# EIS_Main_Radio.net
KiCad netlist of a schematic drawn in Altium Designer
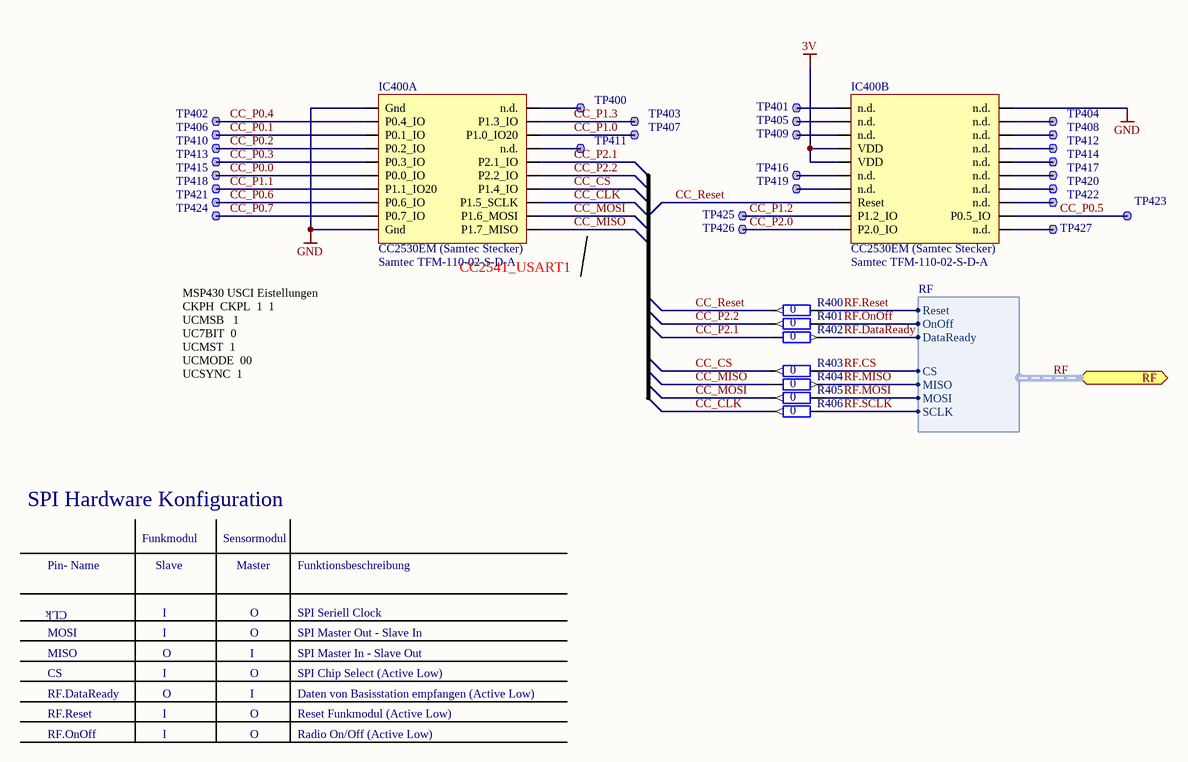
[diagram p0: EIS_Main_Radio.SchDoc]

(export (version "E")
  (design (tool "Eeschema 10.0.6"))
  (components
    (comp (ref "IC400")
      (value "CC2530EM (Samtec Stecker)")
      (footprint "CC2400EM_Board")
      (description "CC2530EM Referenzdesign, Samtec TFM-110-02-S-D-A")
      (fields
        (field (name "01_HERSTELLER") "Samtec TFM-110-02-S-D-A")
        (field (name "09_ERSTELLER") "HSG Rachid Nouna")
      )
      (libsource (lib "RudiSchlibAllg") (part "CC2530EM"))
    )
    (comp (ref "R400")
      (value "0")
      (footprint "RESC1608N")
      (description "RESC1608 (R0603)")
      (libsource (lib "JM_Widerstaende") (part "RESC1608 (R0603)"))
    )
    (comp (ref "R401")
      (value "0")
      (footprint "RESC1608N")
      (description "RESC1608 (R0603)")
      (libsource (lib "JM_Widerstaende") (part "RESC1608 (R0603)"))
    )
    (comp (ref "R402")
      (value "0")
      (footprint "RESC1608N")
      (description "RESC1608 (R0603)")
      (libsource (lib "JM_Widerstaende") (part "RESC1608 (R0603)"))
    )
    (comp (ref "R403")
      (value "0")
      (footprint "RESC1608N")
      (description "RESC1608 (R0603)")
      (libsource (lib "JM_Widerstaende") (part "RESC1608 (R0603)"))
    )
    (comp (ref "R404")
      (value "0")
      (footprint "RESC1608N")
      (description "RESC1608 (R0603)")
      (libsource (lib "JM_Widerstaende") (part "RESC1608 (R0603)"))
    )
    (comp (ref "R405")
      (value "0")
      (footprint "RESC1608N")
      (description "RESC1608 (R0603)")
      (libsource (lib "JM_Widerstaende") (part "RESC1608 (R0603)"))
    )
    (comp (ref "R406")
      (value "0")
      (footprint "RESC1608N")
      (description "RESC1608 (R0603)")
      (libsource (lib "JM_Widerstaende") (part "RESC1608 (R0603)"))
    )
    (comp (ref "TP400")
      (value "Testpoint 1mm")
      (footprint "Testpoint 1mm")
      (libsource (lib "HSG-IMIT_JuergenMerz") (part "Tespoint 1mm"))
    )
    (comp (ref "TP401")
      (value "Testpoint 1mm")
      (footprint "Testpoint 1mm")
      (libsource (lib "HSG-IMIT_JuergenMerz") (part "Tespoint 1mm"))
    )
    (comp (ref "TP402")
      (value "Testpoint 1mm")
      (footprint "Testpoint 1mm")
      (libsource (lib "HSG-IMIT_JuergenMerz") (part "Tespoint 1mm"))
    )
    (comp (ref "TP403")
      (value "Testpoint 1mm")
      (footprint "Testpoint 1mm")
      (libsource (lib "HSG-IMIT_JuergenMerz") (part "Tespoint 1mm"))
    )
    (comp (ref "TP404")
      (value "Testpoint 1mm")
      (footprint "Testpoint 1mm")
      (libsource (lib "HSG-IMIT_JuergenMerz") (part "Tespoint 1mm"))
    )
    (comp (ref "TP405")
      (value "Testpoint 1mm")
      (footprint "Testpoint 1mm")
      (libsource (lib "HSG-IMIT_JuergenMerz") (part "Tespoint 1mm"))
    )
    (comp (ref "TP406")
      (value "Testpoint 1mm")
      (footprint "Testpoint 1mm")
      (libsource (lib "HSG-IMIT_JuergenMerz") (part "Tespoint 1mm"))
    )
    (comp (ref "TP407")
      (value "Testpoint 1mm")
      (footprint "Testpoint 1mm")
      (libsource (lib "HSG-IMIT_JuergenMerz") (part "Tespoint 1mm"))
    )
    (comp (ref "TP408")
      (value "Testpoint 1mm")
      (footprint "Testpoint 1mm")
      (libsource (lib "HSG-IMIT_JuergenMerz") (part "Tespoint 1mm"))
    )
    (comp (ref "TP409")
      (value "Testpoint 1mm")
      (footprint "Testpoint 1mm")
      (libsource (lib "HSG-IMIT_JuergenMerz") (part "Tespoint 1mm"))
    )
    (comp (ref "TP410")
      (value "Testpoint 1mm")
      (footprint "Testpoint 1mm")
      (libsource (lib "HSG-IMIT_JuergenMerz") (part "Tespoint 1mm"))
    )
    (comp (ref "TP411")
      (value "Testpoint 1mm")
      (footprint "Testpoint 1mm")
      (libsource (lib "HSG-IMIT_JuergenMerz") (part "Tespoint 1mm"))
    )
    (comp (ref "TP412")
      (value "Testpoint 1mm")
      (footprint "Testpoint 1mm")
      (libsource (lib "HSG-IMIT_JuergenMerz") (part "Tespoint 1mm"))
    )
    (comp (ref "TP413")
      (value "Testpoint 1mm")
      (footprint "Testpoint 1mm")
      (libsource (lib "HSG-IMIT_JuergenMerz") (part "Tespoint 1mm"))
    )
    (comp (ref "TP414")
      (value "Testpoint 1mm")
      (footprint "Testpoint 1mm")
      (libsource (lib "HSG-IMIT_JuergenMerz") (part "Tespoint 1mm"))
    )
    (comp (ref "TP415")
      (value "Testpoint 1mm")
      (footprint "Testpoint 1mm")
      (libsource (lib "HSG-IMIT_JuergenMerz") (part "Tespoint 1mm"))
    )
    (comp (ref "TP416")
      (value "Testpoint 1mm")
      (footprint "Testpoint 1mm")
      (libsource (lib "HSG-IMIT_JuergenMerz") (part "Tespoint 1mm"))
    )
    (comp (ref "TP417")
      (value "Testpoint 1mm")
      (footprint "Testpoint 1mm")
      (libsource (lib "HSG-IMIT_JuergenMerz") (part "Tespoint 1mm"))
    )
    (comp (ref "TP418")
      (value "Testpoint 1mm")
      (footprint "Testpoint 1mm")
      (libsource (lib "HSG-IMIT_JuergenMerz") (part "Tespoint 1mm"))
    )
    (comp (ref "TP419")
      (value "Testpoint 1mm")
      (footprint "Testpoint 1mm")
      (libsource (lib "HSG-IMIT_JuergenMerz") (part "Tespoint 1mm"))
    )
    (comp (ref "TP420")
      (value "Testpoint 1mm")
      (footprint "Testpoint 1mm")
      (libsource (lib "HSG-IMIT_JuergenMerz") (part "Tespoint 1mm"))
    )
    (comp (ref "TP421")
      (value "Testpoint 1mm")
      (footprint "Testpoint 1mm")
      (libsource (lib "HSG-IMIT_JuergenMerz") (part "Tespoint 1mm"))
    )
    (comp (ref "TP422")
      (value "Testpoint 1mm")
      (footprint "Testpoint 1mm")
      (libsource (lib "HSG-IMIT_JuergenMerz") (part "Tespoint 1mm"))
    )
    (comp (ref "TP423")
      (value "Testpoint 1mm")
      (footprint "Testpoint 1mm")
      (libsource (lib "HSG-IMIT_JuergenMerz") (part "Tespoint 1mm"))
    )
    (comp (ref "TP424")
      (value "Testpoint 1mm")
      (footprint "Testpoint 1mm")
      (libsource (lib "HSG-IMIT_JuergenMerz") (part "Tespoint 1mm"))
    )
    (comp (ref "TP425")
      (value "Testpoint 1mm")
      (footprint "Testpoint 1mm")
      (libsource (lib "HSG-IMIT_JuergenMerz") (part "Tespoint 1mm"))
    )
    (comp (ref "TP426")
      (value "Testpoint 1mm")
      (footprint "Testpoint 1mm")
      (libsource (lib "HSG-IMIT_JuergenMerz") (part "Tespoint 1mm"))
    )
    (comp (ref "TP427")
      (value "Testpoint 1mm")
      (footprint "Testpoint 1mm")
      (libsource (lib "HSG-IMIT_JuergenMerz") (part "Tespoint 1mm"))
    )
  )
  (nets
    (net (code "2") (name "/CC_CLK") (class "Default")
      (node (ref "IC400") (pin "P1_16") (pinfunction "P1.5_SCLK_P1_16") (pintype "passive"))
      (node (ref "R406") (pin "1") (pinfunction "1_1") (pintype "output"))
    )
    (net (code "3") (name "/CC_CS") (class "Default")
      (node (ref "IC400") (pin "P1_14") (pinfunction "P1.4_IO_P1_14") (pintype "passive"))
      (node (ref "R403") (pin "1") (pinfunction "1_1") (pintype "output"))
    )
    (net (code "4") (name "/CC_MISO") (class "Default")
      (node (ref "IC400") (pin "P1_20") (pinfunction "P1.7_MISO_P1_20") (pintype "passive"))
      (node (ref "R404") (pin "1") (pinfunction "1_1") (pintype "output"))
    )
    (net (code "5") (name "/CC_MOSI") (class "Default")
      (node (ref "IC400") (pin "P1_18") (pinfunction "P1.6_MOSI_P1_18") (pintype "passive"))
      (node (ref "R405") (pin "1") (pinfunction "1_1") (pintype "output"))
    )
    (net (code "6") (name "/CC_P0.0") (class "Default")
      (node (ref "IC400") (pin "P1_11") (pinfunction "P0.0_IO_P1_11") (pintype "passive"))
      (node (ref "TP415") (pin "1") (pintype "passive"))
    )
    (net (code "7") (name "/CC_P0.1") (class "Default")
      (node (ref "IC400") (pin "P1_5") (pinfunction "P0.1_IO_P1_5") (pintype "passive"))
      (node (ref "TP406") (pin "1") (pintype "passive"))
    )
    (net (code "8") (name "/CC_P0.2") (class "Default")
      (node (ref "IC400") (pin "P1_7") (pinfunction "P0.2_IO_P1_7") (pintype "passive"))
      (node (ref "TP410") (pin "1") (pintype "passive"))
    )
    (net (code "9") (name "/CC_P0.3") (class "Default")
      (node (ref "IC400") (pin "P1_9") (pinfunction "P0.3_IO_P1_9") (pintype "passive"))
      (node (ref "TP413") (pin "1") (pintype "passive"))
    )
    (net (code "10") (name "/CC_P0.4") (class "Default")
      (node (ref "IC400") (pin "P1_3") (pinfunction "P0.4_IO_P1_3") (pintype "passive"))
      (node (ref "TP402") (pin "1") (pintype "passive"))
    )
    (net (code "11") (name "/CC_P0.5") (class "Default")
      (node (ref "IC400") (pin "P2_18") (pinfunction "P0.5_IO_P2_18") (pintype "passive"))
      (node (ref "TP423") (pin "1") (pintype "passive"))
    )
    (net (code "12") (name "/CC_P0.6") (class "Default")
      (node (ref "IC400") (pin "P1_15") (pinfunction "P0.6_IO_P1_15") (pintype "passive"))
      (node (ref "TP421") (pin "1") (pintype "passive"))
    )
    (net (code "13") (name "/CC_P0.7") (class "Default")
      (node (ref "IC400") (pin "P1_17") (pinfunction "P0.7_IO_P1_17") (pintype "passive"))
      (node (ref "TP424") (pin "1") (pintype "passive"))
    )
    (net (code "14") (name "/CC_P1.0") (class "Default")
      (node (ref "IC400") (pin "P1_6") (pinfunction "P1.0_IO20_P1_6") (pintype "passive"))
      (node (ref "TP407") (pin "1") (pintype "passive"))
    )
    (net (code "15") (name "/CC_P1.1") (class "Default")
      (node (ref "IC400") (pin "P1_13") (pinfunction "P1.1_IO20_P1_13") (pintype "passive"))
      (node (ref "TP418") (pin "1") (pintype "passive"))
    )
    (net (code "16") (name "/CC_P1.2") (class "Default")
      (node (ref "IC400") (pin "P2_17") (pinfunction "P1.2_IO_P2_17") (pintype "passive"))
      (node (ref "TP425") (pin "1") (pintype "passive"))
    )
    (net (code "17") (name "/CC_P1.3") (class "Default")
      (node (ref "IC400") (pin "P1_4") (pinfunction "P1.3_IO_P1_4") (pintype "passive"))
      (node (ref "TP403") (pin "1") (pintype "passive"))
    )
    (net (code "18") (name "/CC_P2.0") (class "Default")
      (node (ref "IC400") (pin "P2_19") (pinfunction "P2.0_IO_P2_19") (pintype "passive"))
      (node (ref "TP426") (pin "1") (pintype "passive"))
    )
    (net (code "19") (name "/CC_P2.1") (class "Default")
      (node (ref "IC400") (pin "P1_10") (pinfunction "P2.1_IO_P1_10") (pintype "passive"))
      (node (ref "R402") (pin "1") (pinfunction "1_1") (pintype "output"))
    )
    (net (code "20") (name "/CC_P2.2") (class "Default")
      (node (ref "IC400") (pin "P1_12") (pinfunction "P2.2_IO_P1_12") (pintype "passive"))
      (node (ref "R401") (pin "1") (pinfunction "1_1") (pintype "output"))
    )
    (net (code "21") (name "/CC_Reset") (class "Default")
      (node (ref "IC400") (pin "P2_15") (pinfunction "Reset_P2_15") (pintype "passive"))
      (node (ref "R400") (pin "1") (pinfunction "1_1") (pintype "output"))
    )
    (net (code "22") (name "/RF.CS") (class "Default")
      (node (ref "R403") (pin "2") (pinfunction "2_2") (pintype "passive"))
    )
    (net (code "23") (name "/RF.DataReady") (class "Default")
      (node (ref "R402") (pin "2") (pinfunction "2_2") (pintype "passive"))
    )
    (net (code "24") (name "/RF.MISO") (class "Default")
      (node (ref "R404") (pin "2") (pinfunction "2_2") (pintype "passive"))
    )
    (net (code "25") (name "/RF.MOSI") (class "Default")
      (node (ref "R405") (pin "2") (pinfunction "2_2") (pintype "passive"))
    )
    (net (code "26") (name "/RF.OnOff") (class "Default")
      (node (ref "R401") (pin "2") (pinfunction "2_2") (pintype "passive"))
    )
    (net (code "27") (name "/RF.Reset") (class "Default")
      (node (ref "R400") (pin "2") (pinfunction "2_2") (pintype "passive"))
    )
    (net (code "28") (name "/RF.SCLK") (class "Default")
      (node (ref "R406") (pin "2") (pinfunction "2_2") (pintype "passive"))
    )
    (net (code "30") (name "3V") (class "Default")
      (node (ref "IC400") (pin "P2_7") (pinfunction "VDD_P2_7") (pintype "power_in"))
      (node (ref "IC400") (pin "P2_9") (pinfunction "VDD_P2_9") (pintype "power_in"))
    )
    (net (code "31") (name "GND") (class "Default")
      (node (ref "IC400") (pin "P1_1") (pinfunction "Gnd_P1_1") (pintype "power_in"))
      (node (ref "IC400") (pin "P1_19") (pinfunction "Gnd_P1_19") (pintype "power_in"))
      (node (ref "IC400") (pin "P2_2") (pinfunction "n.d._P2_2") (pintype "passive"))
    )
    (net (code "32") (name "Net-(IC400A-n.d.-PadP1_2)") (class "Default")
      (node (ref "IC400") (pin "P1_2") (pinfunction "n.d._P1_2") (pintype "passive"))
      (node (ref "TP400") (pin "1") (pintype "passive"))
    )
    (net (code "33") (name "Net-(IC400A-n.d.-PadP1_8)") (class "Default")
      (node (ref "IC400") (pin "P1_8") (pinfunction "n.d._P1_8") (pintype "passive"))
      (node (ref "TP411") (pin "1") (pintype "passive"))
    )
    (net (code "34") (name "Net-(IC400B-n.d.-PadP2_1)") (class "Default")
      (node (ref "IC400") (pin "P2_1") (pinfunction "n.d._P2_1") (pintype "passive"))
      (node (ref "TP401") (pin "1") (pintype "passive"))
    )
    (net (code "35") (name "Net-(IC400B-n.d.-PadP2_3)") (class "Default")
      (node (ref "IC400") (pin "P2_3") (pinfunction "n.d._P2_3") (pintype "passive"))
      (node (ref "TP405") (pin "1") (pintype "passive"))
    )
    (net (code "36") (name "Net-(IC400B-n.d.-PadP2_4)") (class "Default")
      (node (ref "IC400") (pin "P2_4") (pinfunction "n.d._P2_4") (pintype "passive"))
      (node (ref "TP404") (pin "1") (pintype "passive"))
    )
    (net (code "37") (name "Net-(IC400B-n.d.-PadP2_5)") (class "Default")
      (node (ref "IC400") (pin "P2_5") (pinfunction "n.d._P2_5") (pintype "passive"))
      (node (ref "TP409") (pin "1") (pintype "passive"))
    )
    (net (code "38") (name "Net-(IC400B-n.d.-PadP2_6)") (class "Default")
      (node (ref "IC400") (pin "P2_6") (pinfunction "n.d._P2_6") (pintype "passive"))
      (node (ref "TP408") (pin "1") (pintype "passive"))
    )
    (net (code "39") (name "Net-(IC400B-n.d.-PadP2_8)") (class "Default")
      (node (ref "IC400") (pin "P2_8") (pinfunction "n.d._P2_8") (pintype "passive"))
      (node (ref "TP412") (pin "1") (pintype "passive"))
    )
    (net (code "40") (name "Net-(IC400B-n.d.-PadP2_10)") (class "Default")
      (node (ref "IC400") (pin "P2_10") (pinfunction "n.d._P2_10") (pintype "passive"))
      (node (ref "TP414") (pin "1") (pintype "passive"))
    )
    (net (code "41") (name "Net-(IC400B-n.d.-PadP2_11)") (class "Default")
      (node (ref "IC400") (pin "P2_11") (pinfunction "n.d._P2_11") (pintype "passive"))
      (node (ref "TP416") (pin "1") (pintype "passive"))
    )
    (net (code "42") (name "Net-(IC400B-n.d.-PadP2_12)") (class "Default")
      (node (ref "IC400") (pin "P2_12") (pinfunction "n.d._P2_12") (pintype "passive"))
      (node (ref "TP417") (pin "1") (pintype "passive"))
    )
    (net (code "43") (name "Net-(IC400B-n.d.-PadP2_13)") (class "Default")
      (node (ref "IC400") (pin "P2_13") (pinfunction "n.d._P2_13") (pintype "passive"))
      (node (ref "TP419") (pin "1") (pintype "passive"))
    )
    (net (code "44") (name "Net-(IC400B-n.d.-PadP2_14)") (class "Default")
      (node (ref "IC400") (pin "P2_14") (pinfunction "n.d._P2_14") (pintype "passive"))
      (node (ref "TP420") (pin "1") (pintype "passive"))
    )
    (net (code "45") (name "Net-(IC400B-n.d.-PadP2_16)") (class "Default")
      (node (ref "IC400") (pin "P2_16") (pinfunction "n.d._P2_16") (pintype "passive"))
      (node (ref "TP422") (pin "1") (pintype "passive"))
    )
    (net (code "46") (name "Net-(IC400B-n.d.-PadP2_20)") (class "Default")
      (node (ref "IC400") (pin "P2_20") (pinfunction "n.d._P2_20") (pintype "passive"))
      (node (ref "TP427") (pin "1") (pintype "passive"))
    )
  )
)
